# clock_motherboard.net
KiCad netlist of a schematic drawn in EAGLE
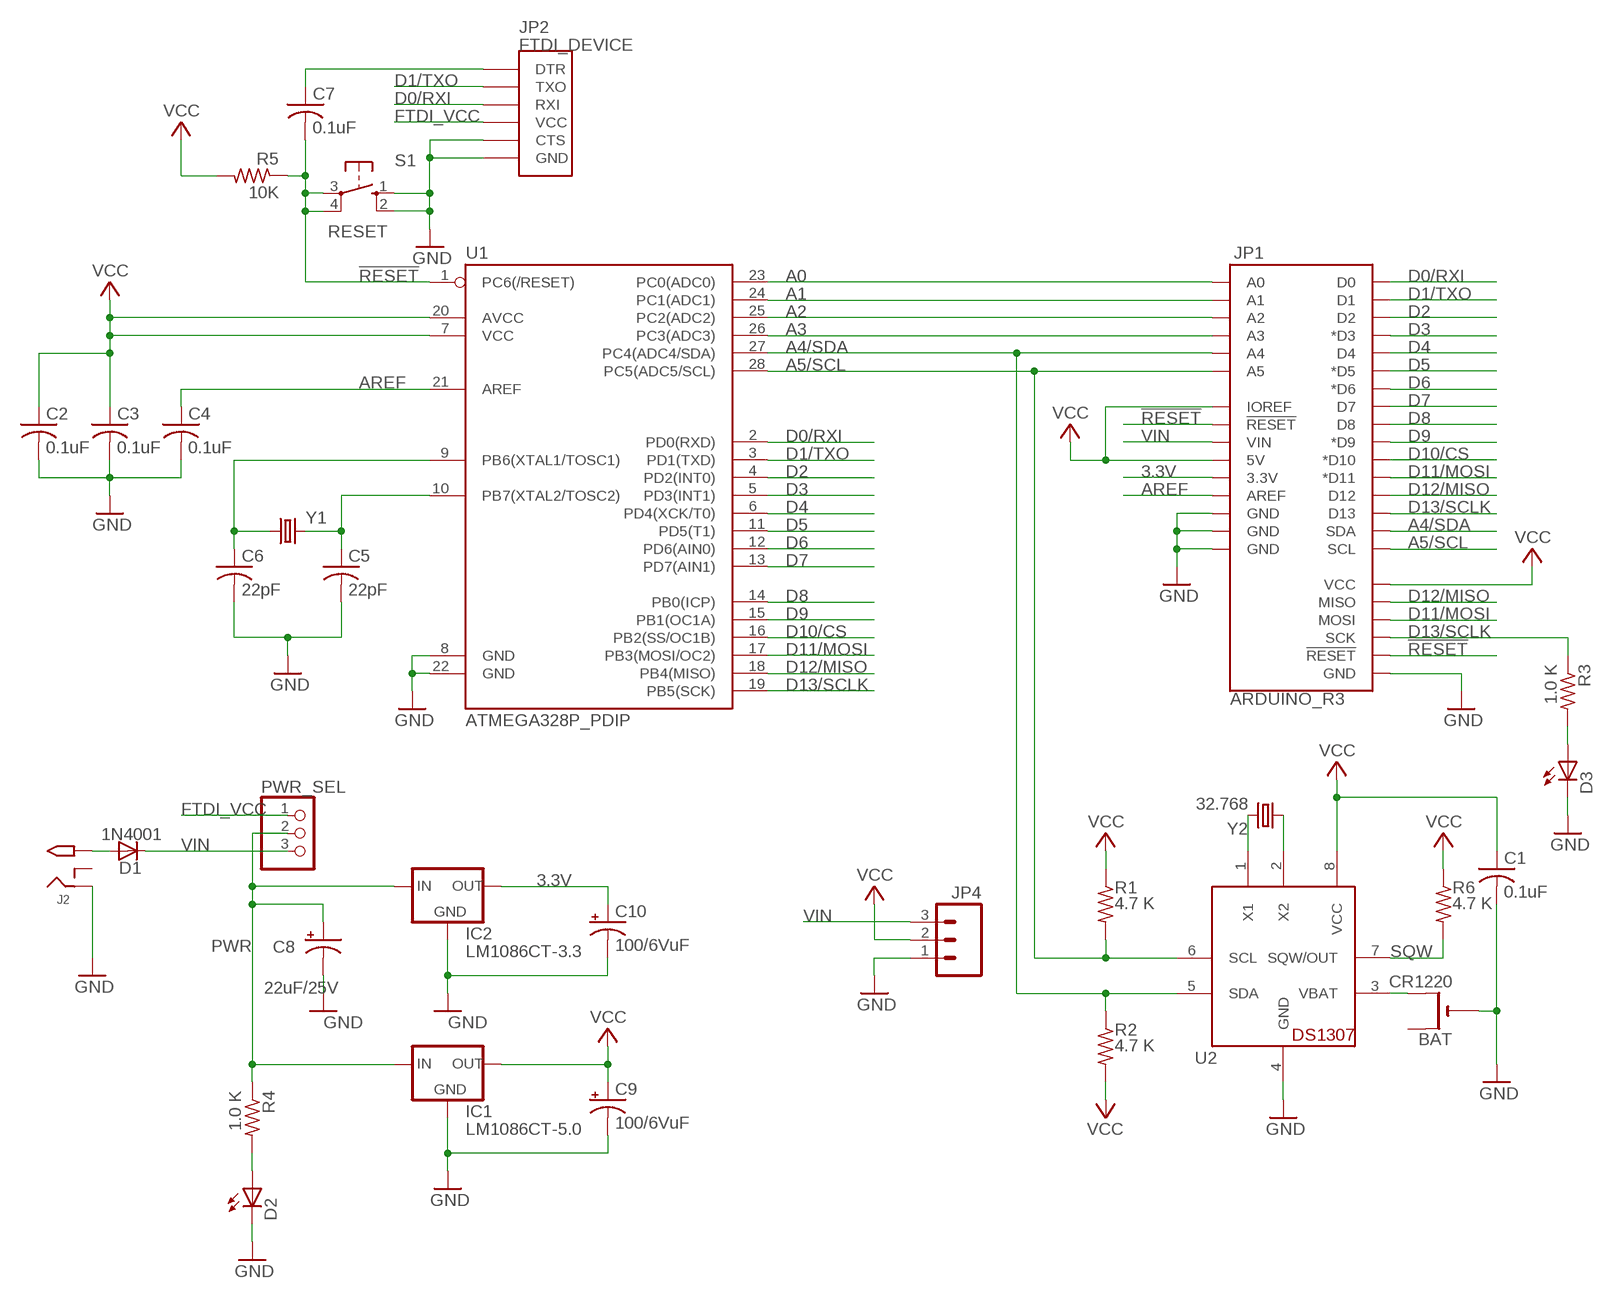
[diagram p0: schematic, sheet 1]

(export (version "E")
  (design (tool "Eeschema 10.0.6"))
  (components
    (comp (ref "BAT")
      (value "CR1220")
      (footprint "eagle-import:CR1220-THM")
      (libsource (lib "eagle-import") (part "CR1220THM"))
    )
    (comp (ref "C1")
      (value "0.1uF")
      (footprint "eagle-import:C025-025X050")
      (libsource (lib "eagle-import") (part "C-US025-025X050"))
    )
    (comp (ref "C2")
      (value "0.1uF")
      (footprint "eagle-import:C025-025X050")
      (libsource (lib "eagle-import") (part "C-US025-025X050"))
    )
    (comp (ref "C3")
      (value "0.1uF")
      (footprint "eagle-import:C025-025X050")
      (libsource (lib "eagle-import") (part "C-US025-025X050"))
    )
    (comp (ref "C4")
      (value "0.1uF")
      (footprint "eagle-import:C025-025X050")
      (libsource (lib "eagle-import") (part "C-US025-025X050"))
    )
    (comp (ref "C5")
      (value "22pF")
      (footprint "eagle-import:C025-025X050")
      (libsource (lib "eagle-import") (part "C-US025-025X050"))
    )
    (comp (ref "C6")
      (value "22pF")
      (footprint "eagle-import:C025-025X050")
      (libsource (lib "eagle-import") (part "C-US025-025X050"))
    )
    (comp (ref "C7")
      (value "0.1uF")
      (footprint "eagle-import:C025-025X050")
      (libsource (lib "eagle-import") (part "C-US025-025X050"))
    )
    (comp (ref "C8")
      (value "22uF/25V")
      (footprint "eagle-import:E2,5-6")
      (libsource (lib "eagle-import") (part "CPOL-USE2.5-6"))
    )
    (comp (ref "C9")
      (value "100/6VuF")
      (footprint "eagle-import:E2,5-6")
      (libsource (lib "eagle-import") (part "CPOL-USE2.5-6"))
    )
    (comp (ref "C10")
      (value "100/6VuF")
      (footprint "eagle-import:E2,5-6")
      (libsource (lib "eagle-import") (part "CPOL-USE2.5-6"))
    )
    (comp (ref "D1")
      (value "1N4001")
      (footprint "eagle-import:DO41-10")
      (libsource (lib "eagle-import") (part "1N4004"))
    )
    (comp (ref "D2")
      (value "LED3MM")
      (footprint "eagle-import:LED3MM")
      (libsource (lib "eagle-import") (part "LED3MM"))
    )
    (comp (ref "D3")
      (value "LED3MM")
      (footprint "eagle-import:LED3MM")
      (libsource (lib "eagle-import") (part "LED3MM"))
    )
    (comp (ref "IC1")
      (value "LM1086CT-5.0")
      (footprint "eagle-import:78XXS")
      (libsource (lib "eagle-import") (part "78XXS"))
    )
    (comp (ref "IC2")
      (value "LM1086CT-3.3")
      (footprint "eagle-import:78XXS")
      (libsource (lib "eagle-import") (part "78XXS"))
    )
    (comp (ref "J2")
      (value "2.1MMJACK")
      (footprint "eagle-import:PJ-102A")
      (libsource (lib "eagle-import") (part "2.1MMJACK"))
    )
    (comp (ref "JP1")
      (value "ARDUINO_R3")
      (footprint "eagle-import:ARDUINO_R3")
      (libsource (lib "eagle-import") (part "ARDUINO_R3"))
    )
    (comp (ref "JP2")
      (value "FTDI_DEVICE")
      (footprint "eagle-import:FTDI_DEVICE_SIDE")
      (libsource (lib "eagle-import") (part "FTDI_DEVICE"))
    )
    (comp (ref "JP4")
      (value "M03SCREW")
      (footprint "eagle-import:SCREWTERMINAL-3.5MM-3")
      (libsource (lib "eagle-import") (part "M03SCREW"))
    )
    (comp (ref "PWR_SEL")
      (value "PINHD-1X3")
      (footprint "eagle-import:1X03")
      (libsource (lib "eagle-import") (part "PINHD-1X3"))
    )
    (comp (ref "R1")
      (value "4.7 K")
      (footprint "eagle-import:0207_5V")
      (libsource (lib "eagle-import") (part "R-US_0207/5V"))
    )
    (comp (ref "R2")
      (value "4.7 K")
      (footprint "eagle-import:0207_5V")
      (libsource (lib "eagle-import") (part "R-US_0207/5V"))
    )
    (comp (ref "R3")
      (value "1.0 K")
      (footprint "eagle-import:0207_5V")
      (libsource (lib "eagle-import") (part "R-US_0207/5V"))
    )
    (comp (ref "R4")
      (value "1.0 K")
      (footprint "eagle-import:0207_5V")
      (libsource (lib "eagle-import") (part "R-US_0207/5V"))
    )
    (comp (ref "R5")
      (value "10K")
      (footprint "eagle-import:0207_5V")
      (libsource (lib "eagle-import") (part "rcl-ez_R-US_0207/5V"))
    )
    (comp (ref "R6")
      (value "4.7 K")
      (footprint "eagle-import:0207_5V")
      (libsource (lib "eagle-import") (part "R-US_0207/5V"))
    )
    (comp (ref "S1")
      (value "RESET")
      (footprint "eagle-import:B3F-10XX")
      (fields (field (name "MPN") "B3F-1000"))
      (libsource (lib "eagle-import") (part "10-XX"))
    )
    (comp (ref "U1")
      (value "ATMEGA328P_PDIP")
      (footprint "eagle-import:DIL28-3")
      (libsource (lib "eagle-import") (part "ATMEGA328P_PDIP"))
    )
    (comp (ref "U2")
      (value "DS1307")
      (footprint "eagle-import:DIL08")
      (libsource (lib "eagle-import") (part "DS1307"))
    )
    (comp (ref "Y1")
      (value "CRYSTALHC49US")
      (footprint "eagle-import:HC49US")
      (libsource (lib "eagle-import") (part "CRYSTALHC49US"))
    )
    (comp (ref "Y2")
      (value "32.768")
      (footprint "eagle-import:TC38H")
      (libsource (lib "eagle-import") (part "CRYTALTC38H"))
    )
  )
  (nets
    (net (code "1") (name "/3.3V") (class "Default")
      (node (ref "C10") (pin "+") (pinfunction "+_+") (pintype "passive"))
      (node (ref "IC2") (pin "OUT") (pinfunction "OUT_OUT") (pintype "passive"))
      (node (ref "JP1") (pin "3.3V") (pinfunction "3.3V_3.3V") (pintype "bidirectional"))
    )
    (net (code "2") (name "/A0") (class "Default")
      (node (ref "JP1") (pin "A0") (pinfunction "A0_A0") (pintype "bidirectional"))
      (node (ref "U1") (pin "23") (pinfunction "PC0(ADC0)_23") (pintype "bidirectional"))
    )
    (net (code "3") (name "/A1") (class "Default")
      (node (ref "JP1") (pin "A1") (pinfunction "A1_A1") (pintype "bidirectional"))
      (node (ref "U1") (pin "24") (pinfunction "PC1(ADC1)_24") (pintype "bidirectional"))
    )
    (net (code "4") (name "/A2") (class "Default")
      (node (ref "JP1") (pin "A2") (pinfunction "A2_A2") (pintype "bidirectional"))
      (node (ref "U1") (pin "25") (pinfunction "PC2(ADC2)_25") (pintype "bidirectional"))
    )
    (net (code "5") (name "/A3") (class "Default")
      (node (ref "JP1") (pin "A3") (pinfunction "A3_A3") (pintype "bidirectional"))
      (node (ref "U1") (pin "26") (pinfunction "PC3(ADC3)_26") (pintype "bidirectional"))
    )
    (net (code "6") (name "/A4{slash}SDA") (class "Default")
      (node (ref "JP1") (pin "A4") (pinfunction "A4_A4") (pintype "bidirectional"))
      (node (ref "JP1") (pin "SDA") (pinfunction "SDA_SDA") (pintype "bidirectional"))
      (node (ref "R2") (pin "1") (pinfunction "1_1") (pintype "passive"))
      (node (ref "U1") (pin "27") (pinfunction "PC4(ADC4/SDA)_27") (pintype "bidirectional"))
      (node (ref "U2") (pin "5") (pinfunction "SDA_5") (pintype "bidirectional"))
    )
    (net (code "7") (name "/A5{slash}SCL") (class "Default")
      (node (ref "JP1") (pin "A5") (pinfunction "A5_A5") (pintype "bidirectional"))
      (node (ref "JP1") (pin "SCL") (pinfunction "SCL_SCL") (pintype "bidirectional"))
      (node (ref "R1") (pin "2") (pinfunction "2_2") (pintype "passive"))
      (node (ref "U1") (pin "28") (pinfunction "PC5(ADC5/SCL)_28") (pintype "bidirectional"))
      (node (ref "U2") (pin "6") (pinfunction "SCL_6") (pintype "bidirectional"))
    )
    (net (code "8") (name "/AREF") (class "Default")
      (node (ref "C4") (pin "1") (pinfunction "1_1") (pintype "passive"))
      (node (ref "JP1") (pin "AREF") (pinfunction "AREF_AREF") (pintype "bidirectional"))
      (node (ref "U1") (pin "21") (pinfunction "AREF_21") (pintype "bidirectional"))
    )
    (net (code "9") (name "/D0{slash}RXI") (class "Default")
      (node (ref "JP1") (pin "D0") (pinfunction "D0_D0") (pintype "bidirectional"))
      (node (ref "JP2") (pin "P$3") (pinfunction "RXI_P$3") (pintype "bidirectional"))
      (node (ref "U1") (pin "2") (pinfunction "PD0(RXD)_2") (pintype "bidirectional"))
    )
    (net (code "10") (name "/D1{slash}TXO") (class "Default")
      (node (ref "JP1") (pin "D1") (pinfunction "D1_D1") (pintype "bidirectional"))
      (node (ref "JP2") (pin "P$2") (pinfunction "TXO_P$2") (pintype "bidirectional"))
      (node (ref "U1") (pin "3") (pinfunction "PD1(TXD)_3") (pintype "bidirectional"))
    )
    (net (code "11") (name "/D2") (class "Default")
      (node (ref "JP1") (pin "D2") (pinfunction "D2_D2") (pintype "bidirectional"))
      (node (ref "U1") (pin "4") (pinfunction "PD2(INT0)_4") (pintype "bidirectional"))
    )
    (net (code "12") (name "/D3") (class "Default")
      (node (ref "JP1") (pin "D3") (pinfunction "*D3_D3") (pintype "bidirectional"))
      (node (ref "U1") (pin "5") (pinfunction "PD3(INT1)_5") (pintype "bidirectional"))
    )
    (net (code "13") (name "/D4") (class "Default")
      (node (ref "JP1") (pin "D4") (pinfunction "D4_D4") (pintype "bidirectional"))
      (node (ref "U1") (pin "6") (pinfunction "PD4(XCK/T0)_6") (pintype "bidirectional"))
    )
    (net (code "14") (name "/D5") (class "Default")
      (node (ref "JP1") (pin "D5") (pinfunction "*D5_D5") (pintype "bidirectional"))
      (node (ref "U1") (pin "11") (pinfunction "PD5(T1)_11") (pintype "bidirectional"))
    )
    (net (code "15") (name "/D6") (class "Default")
      (node (ref "JP1") (pin "D6") (pinfunction "*D6_D6") (pintype "bidirectional"))
      (node (ref "U1") (pin "12") (pinfunction "PD6(AIN0)_12") (pintype "bidirectional"))
    )
    (net (code "16") (name "/D7") (class "Default")
      (node (ref "JP1") (pin "D7") (pinfunction "D7_D7") (pintype "bidirectional"))
      (node (ref "U1") (pin "13") (pinfunction "PD7(AIN1)_13") (pintype "bidirectional"))
    )
    (net (code "17") (name "/D8") (class "Default")
      (node (ref "JP1") (pin "D8") (pinfunction "D8_D8") (pintype "bidirectional"))
      (node (ref "U1") (pin "14") (pinfunction "PB0(ICP)_14") (pintype "bidirectional"))
    )
    (net (code "18") (name "/D9") (class "Default")
      (node (ref "JP1") (pin "D9") (pinfunction "*D9_D9") (pintype "bidirectional"))
      (node (ref "U1") (pin "15") (pinfunction "PB1(OC1A)_15") (pintype "bidirectional"))
    )
    (net (code "19") (name "/D10{slash}CS") (class "Default")
      (node (ref "JP1") (pin "D10") (pinfunction "*D10_D10") (pintype "bidirectional"))
      (node (ref "U1") (pin "16") (pinfunction "PB2(SS/OC1B)_16") (pintype "bidirectional"))
    )
    (net (code "20") (name "/D11{slash}MOSI") (class "Default")
      (node (ref "JP1") (pin "D11") (pinfunction "*D11_D11") (pintype "bidirectional"))
      (node (ref "JP1") (pin "MOSI") (pinfunction "MOSI_MOSI") (pintype "bidirectional"))
      (node (ref "U1") (pin "17") (pinfunction "PB3(MOSI/OC2)_17") (pintype "bidirectional"))
    )
    (net (code "21") (name "/D12{slash}MISO") (class "Default")
      (node (ref "JP1") (pin "D12") (pinfunction "D12_D12") (pintype "bidirectional"))
      (node (ref "JP1") (pin "MISO") (pinfunction "MISO_MISO") (pintype "bidirectional"))
      (node (ref "U1") (pin "18") (pinfunction "PB4(MISO)_18") (pintype "bidirectional"))
    )
    (net (code "22") (name "/D13{slash}SCLK") (class "Default")
      (node (ref "JP1") (pin "D13") (pinfunction "D13_D13") (pintype "bidirectional"))
      (node (ref "JP1") (pin "SCK") (pinfunction "SCK_SCK") (pintype "bidirectional"))
      (node (ref "R3") (pin "1") (pinfunction "1_1") (pintype "passive"))
      (node (ref "U1") (pin "19") (pinfunction "PB5(SCK)_19") (pintype "bidirectional"))
    )
    (net (code "23") (name "/FTDI_VCC") (class "Default")
      (node (ref "JP2") (pin "P$4") (pinfunction "VCC_P$4") (pintype "bidirectional"))
      (node (ref "PWR_SEL") (pin "1") (pinfunction "1_1") (pintype "passive"))
    )
    (net (code "24") (name "/PWR") (class "Default")
      (node (ref "C8") (pin "+") (pinfunction "+_+") (pintype "passive"))
      (node (ref "IC1") (pin "IN") (pinfunction "IN_IN") (pintype "input"))
      (node (ref "IC2") (pin "IN") (pinfunction "IN_IN") (pintype "input"))
      (node (ref "PWR_SEL") (pin "2") (pinfunction "2_2") (pintype "passive"))
      (node (ref "R4") (pin "1") (pinfunction "1_1") (pintype "passive"))
    )
    (net (code "25") (name "/SQW") (class "Default")
      (node (ref "R6") (pin "2") (pinfunction "2_2") (pintype "passive"))
      (node (ref "U2") (pin "7") (pinfunction "SQW/OUT_7") (pintype "bidirectional"))
    )
    (net (code "26") (name "/VIN") (class "Default")
      (node (ref "D1") (pin "C") (pinfunction "C_C") (pintype "passive"))
      (node (ref "JP1") (pin "VIN") (pinfunction "VIN_VIN") (pintype "bidirectional"))
      (node (ref "JP4") (pin "3") (pinfunction "3_3") (pintype "passive"))
      (node (ref "PWR_SEL") (pin "3") (pinfunction "3_3") (pintype "passive"))
    )
    (net (code "27") (name "/~{RESET}") (class "Default")
      (node (ref "C7") (pin "2") (pinfunction "2_2") (pintype "passive"))
      (node (ref "JP1") (pin "RESET@1") (pinfunction "~{RESET}_RESET@1") (pintype "bidirectional"))
      (node (ref "JP1") (pin "RESET@2") (pinfunction "~{RESET}_RESET@2") (pintype "bidirectional"))
      (node (ref "R5") (pin "1") (pinfunction "1_1") (pintype "passive"))
      (node (ref "S1") (pin "3") (pinfunction "P_3") (pintype "passive"))
      (node (ref "S1") (pin "4") (pinfunction "P1_4") (pintype "passive"))
      (node (ref "U1") (pin "1") (pinfunction "PC6(/RESET)_1") (pintype "bidirectional"))
    )
    (net (code "28") (name "GND") (class "Default")
      (node (ref "BAT") (pin "-") (pinfunction "-_-") (pintype "passive"))
      (node (ref "C1") (pin "2") (pinfunction "2_2") (pintype "passive"))
      (node (ref "C10") (pin "-") (pinfunction "-_-") (pintype "passive"))
      (node (ref "C2") (pin "2") (pinfunction "2_2") (pintype "passive"))
      (node (ref "C3") (pin "2") (pinfunction "2_2") (pintype "passive"))
      (node (ref "C4") (pin "2") (pinfunction "2_2") (pintype "passive"))
      (node (ref "C5") (pin "2") (pinfunction "2_2") (pintype "passive"))
      (node (ref "C6") (pin "2") (pinfunction "2_2") (pintype "passive"))
      (node (ref "C8") (pin "-") (pinfunction "-_-") (pintype "passive"))
      (node (ref "C9") (pin "-") (pinfunction "-_-") (pintype "passive"))
      (node (ref "D2") (pin "K") (pinfunction "C_K") (pintype "passive"))
      (node (ref "D3") (pin "K") (pinfunction "C_K") (pintype "passive"))
      (node (ref "IC1") (pin "GND") (pinfunction "GND_GND") (pintype "input"))
      (node (ref "IC2") (pin "GND") (pinfunction "GND_GND") (pintype "input"))
      (node (ref "J2") (pin "RING") (pinfunction "RING_RING") (pintype "bidirectional"))
      (node (ref "JP1") (pin "GND@1") (pinfunction "GND_GND@1") (pintype "bidirectional"))
      (node (ref "JP1") (pin "GND@2") (pinfunction "GND_GND@2") (pintype "bidirectional"))
      (node (ref "JP1") (pin "GND@3") (pinfunction "GND_GND@3") (pintype "bidirectional"))
      (node (ref "JP1") (pin "GND@4") (pinfunction "GND_GND@4") (pintype "bidirectional"))
      (node (ref "JP2") (pin "P$5") (pinfunction "CTS_P$5") (pintype "bidirectional"))
      (node (ref "JP2") (pin "P$6") (pinfunction "GND_P$6") (pintype "bidirectional"))
      (node (ref "JP4") (pin "1") (pinfunction "1_1") (pintype "passive"))
      (node (ref "S1") (pin "1") (pinfunction "S_1") (pintype "passive"))
      (node (ref "S1") (pin "2") (pinfunction "S1_2") (pintype "passive"))
      (node (ref "U1") (pin "22") (pinfunction "GND_22") (pintype "bidirectional"))
      (node (ref "U1") (pin "8") (pinfunction "GND_8") (pintype "bidirectional"))
      (node (ref "U2") (pin "4") (pinfunction "GND_4") (pintype "power_in"))
    )
    (net (code "29") (name "Net-(BAT-+1)") (class "Default")
      (node (ref "BAT") (pin "+2") (pinfunction "+1_+2") (pintype "passive"))
      (node (ref "U2") (pin "3") (pinfunction "VBAT_3") (pintype "power_in"))
    )
    (net (code "30") (name "Net-(D1-PadA)") (class "Default")
      (node (ref "D1") (pin "A") (pinfunction "A_A") (pintype "passive"))
      (node (ref "J2") (pin "TIP") (pinfunction "TIP_TIP") (pintype "bidirectional"))
    )
    (net (code "31") (name "Net-(D2-PadA)") (class "Default")
      (node (ref "D2") (pin "A") (pinfunction "A_A") (pintype "passive"))
      (node (ref "R4") (pin "2") (pinfunction "2_2") (pintype "passive"))
    )
    (net (code "32") (name "Net-(D3-PadA)") (class "Default")
      (node (ref "D3") (pin "A") (pinfunction "A_A") (pintype "passive"))
      (node (ref "R3") (pin "2") (pinfunction "2_2") (pintype "passive"))
    )
    (net (code "33") (name "Net-(JP2-DTR)") (class "Default")
      (node (ref "C7") (pin "1") (pinfunction "1_1") (pintype "passive"))
      (node (ref "JP2") (pin "P$1") (pinfunction "DTR_P$1") (pintype "bidirectional"))
    )
    (net (code "34") (name "Net-(U1-PB6(XTAL1{slash}TOSC1))") (class "Default")
      (node (ref "C6") (pin "1") (pinfunction "1_1") (pintype "passive"))
      (node (ref "U1") (pin "9") (pinfunction "PB6(XTAL1/TOSC1)_9") (pintype "bidirectional"))
      (node (ref "Y1") (pin "1") (pinfunction "1_1") (pintype "passive"))
    )
    (net (code "35") (name "Net-(U1-PB7(XTAL2{slash}TOSC2))") (class "Default")
      (node (ref "C5") (pin "1") (pinfunction "1_1") (pintype "passive"))
      (node (ref "U1") (pin "10") (pinfunction "PB7(XTAL2/TOSC2)_10") (pintype "bidirectional"))
      (node (ref "Y1") (pin "2") (pinfunction "2_2") (pintype "passive"))
    )
    (net (code "36") (name "Net-(U2-X1)") (class "Default")
      (node (ref "U2") (pin "1") (pinfunction "X1_1") (pintype "passive"))
      (node (ref "Y2") (pin "2") (pinfunction "2_2") (pintype "passive"))
    )
    (net (code "37") (name "Net-(U2-X2)") (class "Default")
      (node (ref "U2") (pin "2") (pinfunction "X2_2") (pintype "passive"))
      (node (ref "Y2") (pin "1") (pinfunction "1_1") (pintype "passive"))
    )
    (net (code "38") (name "VCC") (class "Default")
      (node (ref "C1") (pin "1") (pinfunction "1_1") (pintype "passive"))
      (node (ref "C2") (pin "1") (pinfunction "1_1") (pintype "passive"))
      (node (ref "C3") (pin "1") (pinfunction "1_1") (pintype "passive"))
      (node (ref "C9") (pin "+") (pinfunction "+_+") (pintype "passive"))
      (node (ref "IC1") (pin "OUT") (pinfunction "OUT_OUT") (pintype "passive"))
      (node (ref "JP1") (pin "5V") (pinfunction "5V_5V") (pintype "bidirectional"))
      (node (ref "JP1") (pin "IOREF") (pinfunction "IOREF_IOREF") (pintype "bidirectional"))
      (node (ref "JP1") (pin "VCC") (pinfunction "VCC_VCC") (pintype "bidirectional"))
      (node (ref "JP4") (pin "2") (pinfunction "2_2") (pintype "passive"))
      (node (ref "R1") (pin "1") (pinfunction "1_1") (pintype "passive"))
      (node (ref "R2") (pin "2") (pinfunction "2_2") (pintype "passive"))
      (node (ref "R5") (pin "2") (pinfunction "2_2") (pintype "passive"))
      (node (ref "R6") (pin "1") (pinfunction "1_1") (pintype "passive"))
      (node (ref "U1") (pin "20") (pinfunction "AVCC_20") (pintype "bidirectional"))
      (node (ref "U1") (pin "7") (pinfunction "VCC_7") (pintype "bidirectional"))
      (node (ref "U2") (pin "8") (pinfunction "VCC_8") (pintype "power_in"))
    )
    (net (code "39") (name "unconnected-(BAT-+-Pad+1)") (class "Default")
      (node (ref "BAT") (pin "+1") (pinfunction "+_+1") (pintype "passive"))
    )
    (net (code "40") (name "unconnected-(J2-PadRING_SW)") (class "Default")
      (node (ref "J2") (pin "RING_SW") (pinfunction "RING_SW_RING_SW") (pintype "bidirectional"))
    )
  )
)
